# 06-RP2040.net
KiCad netlist of a schematic drawn in Altium Designer
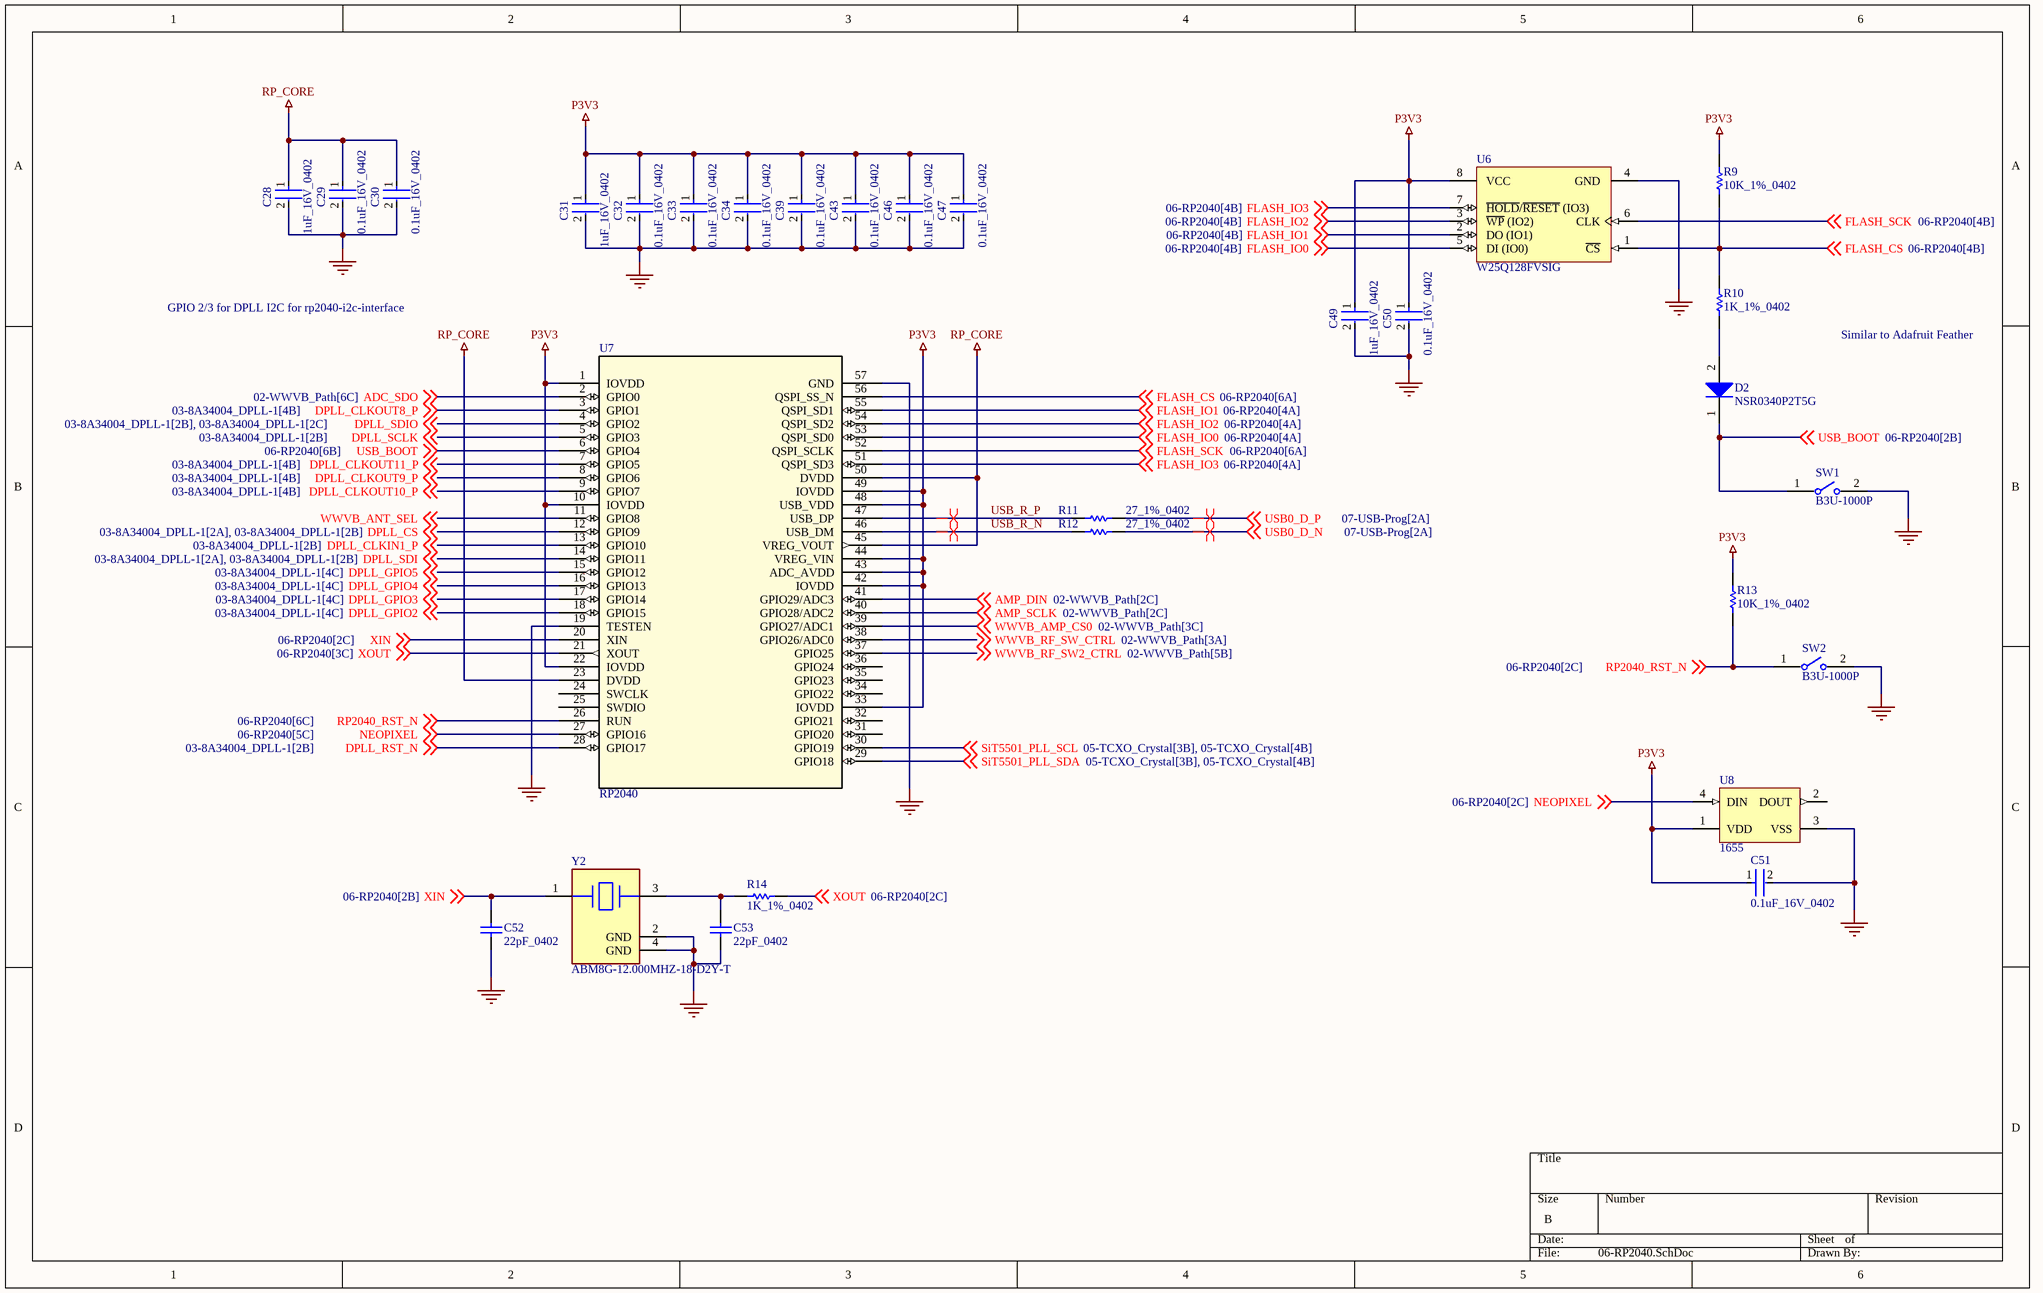
[diagram p0: 06-RP2040.SchDoc]

(export (version "E")
  (design (tool "Eeschema 10.0.6"))
  (components
    (comp (ref "C28")
      (value "1uF_16V_0402")
      (footprint "FP-0402-L_1_0_0_05-W_0_5-IPC_A")
      (description "None")
      (fields (field (name "TOLERANCE") "10%"))
      (libsource (lib "Altium Content Vault") (part "b4654b650e69147ec39a6b967a45e02"))
    )
    (comp (ref "C29")
      (value "0.1uF_16V_0402")
      (footprint "FP-C0402-BB-MFG")
      (description "CAP CER 0.1UF 16V 5% X7R 0402")
      (fields
        (field (name "MANUFACTURER") "Kemet")
        (field (name "MANUFACTURER PART NUMBER") "C0402C104J4RACTU")
      )
      (libsource (lib "Altium Content Vault") (part "b4654b650e69147ec39a6b967a45e02"))
    )
    (comp (ref "C30")
      (value "0.1uF_16V_0402")
      (footprint "FP-C0402-BB-MFG")
      (description "CAP CER 0.1UF 16V 5% X7R 0402")
      (fields
        (field (name "MANUFACTURER") "Kemet")
        (field (name "MANUFACTURER PART NUMBER") "C0402C104J4RACTU")
      )
      (libsource (lib "Altium Content Vault") (part "b4654b650e69147ec39a6b967a45e02"))
    )
    (comp (ref "C31")
      (value "1uF_16V_0402")
      (footprint "FP-0402-L_1_0_0_05-W_0_5-IPC_A")
      (description "None")
      (fields (field (name "TOLERANCE") "10%"))
      (libsource (lib "Altium Content Vault") (part "b4654b650e69147ec39a6b967a45e02"))
    )
    (comp (ref "C32")
      (value "0.1uF_16V_0402")
      (footprint "FP-C0402-BB-MFG")
      (description "CAP CER 0.1UF 16V 5% X7R 0402")
      (fields
        (field (name "MANUFACTURER") "Kemet")
        (field (name "MANUFACTURER PART NUMBER") "C0402C104J4RACTU")
      )
      (libsource (lib "Altium Content Vault") (part "b4654b650e69147ec39a6b967a45e02"))
    )
    (comp (ref "C33")
      (value "0.1uF_16V_0402")
      (footprint "FP-C0402-BB-MFG")
      (description "CAP CER 0.1UF 16V 5% X7R 0402")
      (fields
        (field (name "MANUFACTURER") "Kemet")
        (field (name "MANUFACTURER PART NUMBER") "C0402C104J4RACTU")
      )
      (libsource (lib "Altium Content Vault") (part "b4654b650e69147ec39a6b967a45e02"))
    )
    (comp (ref "C34")
      (value "0.1uF_16V_0402")
      (footprint "FP-C0402-BB-MFG")
      (description "CAP CER 0.1UF 16V 5% X7R 0402")
      (fields
        (field (name "MANUFACTURER") "Kemet")
        (field (name "MANUFACTURER PART NUMBER") "C0402C104J4RACTU")
      )
      (libsource (lib "Altium Content Vault") (part "b4654b650e69147ec39a6b967a45e02"))
    )
    (comp (ref "C39")
      (value "0.1uF_16V_0402")
      (footprint "FP-C0402-BB-MFG")
      (description "CAP CER 0.1UF 16V 5% X7R 0402")
      (fields
        (field (name "MANUFACTURER") "Kemet")
        (field (name "MANUFACTURER PART NUMBER") "C0402C104J4RACTU")
      )
      (libsource (lib "Altium Content Vault") (part "b4654b650e69147ec39a6b967a45e02"))
    )
    (comp (ref "C43")
      (value "0.1uF_16V_0402")
      (footprint "FP-C0402-BB-MFG")
      (description "CAP CER 0.1UF 16V 5% X7R 0402")
      (fields
        (field (name "MANUFACTURER") "Kemet")
        (field (name "MANUFACTURER PART NUMBER") "C0402C104J4RACTU")
      )
      (libsource (lib "Altium Content Vault") (part "b4654b650e69147ec39a6b967a45e02"))
    )
    (comp (ref "C46")
      (value "0.1uF_16V_0402")
      (footprint "FP-C0402-BB-MFG")
      (description "CAP CER 0.1UF 16V 5% X7R 0402")
      (fields
        (field (name "MANUFACTURER") "Kemet")
        (field (name "MANUFACTURER PART NUMBER") "C0402C104J4RACTU")
      )
      (libsource (lib "Altium Content Vault") (part "b4654b650e69147ec39a6b967a45e02"))
    )
    (comp (ref "C47")
      (value "0.1uF_16V_0402")
      (footprint "FP-C0402-BB-MFG")
      (description "CAP CER 0.1UF 16V 5% X7R 0402")
      (fields
        (field (name "MANUFACTURER") "Kemet")
        (field (name "MANUFACTURER PART NUMBER") "C0402C104J4RACTU")
      )
      (libsource (lib "Altium Content Vault") (part "b4654b650e69147ec39a6b967a45e02"))
    )
    (comp (ref "C49")
      (value "1uF_16V_0402")
      (footprint "FP-0402-L_1_0_0_05-W_0_5-IPC_A")
      (description "None")
      (fields (field (name "TOLERANCE") "10%"))
      (libsource (lib "Altium Content Vault") (part "b4654b650e69147ec39a6b967a45e02"))
    )
    (comp (ref "C50")
      (value "0.1uF_16V_0402")
      (footprint "FP-C0402-BB-MFG")
      (description "CAP CER 0.1UF 16V 5% X7R 0402")
      (fields
        (field (name "MANUFACTURER") "Kemet")
        (field (name "MANUFACTURER PART NUMBER") "C0402C104J4RACTU")
      )
      (libsource (lib "Altium Content Vault") (part "b4654b650e69147ec39a6b967a45e02"))
    )
    (comp (ref "C51")
      (value "0.1uF_16V_0402")
      (footprint "FP-C0402-BB-MFG")
      (description "CAP CER 0.1UF 16V 5% X7R 0402")
      (fields
        (field (name "MANUFACTURER") "Kemet")
        (field (name "MANUFACTURER PART NUMBER") "C0402C104J4RACTU")
      )
      (libsource (lib "Altium Content Vault") (part "b4654b650e69147ec39a6b967a45e02"))
    )
    (comp (ref "C52")
      (value "22pF_0402")
      (footprint "CAPC1005X55X25ML05T05")
      (description "Chip Capacitor, 22 pF, +/- 5%, 50 V, -55 to 125 degC, 0402 (1005 Metric), RoHS, Tape and Reel")
      (fields (field (name "MANUFACTURER") "Yageo") (field (name "TOLERANCE") "5%"))
      (libsource (lib "Altium Content Vault") (part "CAP-NP-2"))
    )
    (comp (ref "C53")
      (value "22pF_0402")
      (footprint "CAPC1005X55X25ML05T05")
      (description "Chip Capacitor, 22 pF, +/- 5%, 50 V, -55 to 125 degC, 0402 (1005 Metric), RoHS, Tape and Reel")
      (fields (field (name "MANUFACTURER") "Yageo") (field (name "TOLERANCE") "5%"))
      (libsource (lib "Altium Content Vault") (part "CAP-NP-2"))
    )
    (comp (ref "D2")
      (value "NSR0340P2T5G")
      (footprint "ONSC-SOD-923-2-514AB-01_B_V")
      (description "Schottky Barrier Diode, 2-Pin SOD-923, Pb-Free, Tape and Reel")
      (fields (field (name "MANUFACTURER") "On Semiconductor"))
      (libsource (lib "Altium Content Vault") (part "ONSC-D-K1A2-2"))
    )
    (comp (ref "R9")
      (value "10K_1%_0402")
      (footprint "RESC1005X40X25NL10T10")
      (fields (field (name "MANUFACTURER") "Bourns") (field (name "PART NUMBER") "CR0402-FX-1002GLF"))
      (libsource (lib "Altium Content Vault") (part "RES"))
    )
    (comp (ref "R10")
      (value "1K_1%_0402")
      (footprint "RESC1005X40X25LL10T10")
      (fields (field (name "PART NUMBER") "CR0402-FX-1001GLF") (field (name "MANUFACTURER") "Bourns"))
      (libsource (lib "Altium Content Vault") (part "RES"))
    )
    (comp (ref "R11")
      (value "27_1%_0402")
      (footprint "RESC1005X40X25LL05T10")
      (fields (field (name "PART NUMBER") "RC0402FR-0727RL") (field (name "MANUFACTURER") "Yageo / Phycomp"))
      (libsource (lib "Altium Content Vault") (part "RES"))
    )
    (comp (ref "R12")
      (value "27_1%_0402")
      (footprint "RESC1005X40X25LL05T10")
      (fields (field (name "PART NUMBER") "RC0402FR-0727RL") (field (name "MANUFACTURER") "Yageo / Phycomp"))
      (libsource (lib "Altium Content Vault") (part "RES"))
    )
    (comp (ref "R13")
      (value "10K_1%_0402")
      (footprint "RESC1005X40X25NL10T10")
      (fields (field (name "MANUFACTURER") "Bourns") (field (name "PART NUMBER") "CR0402-FX-1002GLF"))
      (libsource (lib "Altium Content Vault") (part "RES"))
    )
    (comp (ref "R14")
      (value "1K_1%_0402")
      (footprint "RESC1005X40X25LL10T10")
      (fields (field (name "PART NUMBER") "CR0402-FX-1001GLF") (field (name "MANUFACTURER") "Bourns"))
      (libsource (lib "Altium Content Vault") (part "RES"))
    )
    (comp (ref "SW1")
      (value "B3U-1000P")
      (footprint "FP-B3U-1000P-MFG")
      (description "SWITCH TACTILE SPST-NO 0.05A 12V")
      (libsource (lib "Altium Content Vault") (part "ae622034201233ca1abcedc05908f33"))
    )
    (comp (ref "SW2")
      (value "B3U-1000P")
      (footprint "FP-B3U-1000P-MFG")
      (description "SWITCH TACTILE SPST-NO 0.05A 12V")
      (libsource (lib "Altium Content Vault") (part "ae622034201233ca1abcedc05908f33"))
    )
    (comp (ref "U6")
      (value "W25Q128FVSIG")
      (footprint "WINB-SOIC-8_M")
      (fields (field (name "MANUFACTURER") "Winbond"))
      (libsource (lib "Altium Content Vault") (part "WINB-W25Q128FVSIG-SOIC-8"))
    )
    (comp (ref "U7")
      (value "RP2040")
      (footprint "IC57_RP2040")
      (description "No Description Available")
      (libsource (lib "RP2040") (part "RP2040"))
    )
    (comp (ref "U8")
      (value "1655")
      (footprint "ADA-RGB-1655_V")
      (fields (field (name "MANUFACTURER") "Adafruit-Industries-LLC"))
      (libsource (lib "Altium Content Vault") (part "ADA-RGB-1655-4"))
    )
    (comp (ref "Y2")
      (value "ABM8G-12.000MHZ-18-D2Y-T")
      (footprint "FP-ABM8G-MFG")
      (description "Crystal 12MHz ±20ppm (Tol) ±30ppm (Stability) 18pF FUND 120Ω 4-Pin SMD T/R")
      (fields (field (name "TOLERANCE") "20ppm"))
      (libsource (lib "Altium Content Vault") (part "48e526d86b7f2615d98721063c72f49"))
    )
  )
  (nets
    (net (code "1") (name "/USB_R_N") (class "Default")
      (node (ref "R12") (pin "1") (pinfunction "1_1") (pintype "passive"))
      (node (ref "U7") (pin "46") (pinfunction "USB_DM_46") (pintype "passive"))
    )
    (net (code "2") (name "/USB_R_P") (class "Default")
      (node (ref "R11") (pin "1") (pinfunction "1_1") (pintype "passive"))
      (node (ref "U7") (pin "47") (pinfunction "USB_DP_47") (pintype "passive"))
    )
    (net (code "3") (name "ADC_SDO") (class "Default")
      (node (ref "U7") (pin "2") (pinfunction "GPIO0_2") (pintype "bidirectional"))
    )
    (net (code "4") (name "AMP_DIN") (class "Default")
      (node (ref "U7") (pin "41") (pinfunction "GPIO29/ADC3_41") (pintype "bidirectional"))
    )
    (net (code "5") (name "AMP_SCLK") (class "Default")
      (node (ref "U7") (pin "40") (pinfunction "GPIO28/ADC2_40") (pintype "bidirectional"))
    )
    (net (code "6") (name "DPLL_CLKIN1_P") (class "Default")
      (node (ref "U7") (pin "13") (pinfunction "GPIO10_13") (pintype "bidirectional"))
    )
    (net (code "7") (name "DPLL_CLKOUT8_P") (class "Default")
      (node (ref "U7") (pin "3") (pinfunction "GPIO1_3") (pintype "bidirectional"))
    )
    (net (code "8") (name "DPLL_CLKOUT9_P") (class "Default")
      (node (ref "U7") (pin "8") (pinfunction "GPIO6_8") (pintype "bidirectional"))
    )
    (net (code "9") (name "DPLL_CLKOUT10_P") (class "Default")
      (node (ref "U7") (pin "9") (pinfunction "GPIO7_9") (pintype "bidirectional"))
    )
    (net (code "10") (name "DPLL_CLKOUT11_P") (class "Default")
      (node (ref "U7") (pin "7") (pinfunction "GPIO5_7") (pintype "bidirectional"))
    )
    (net (code "11") (name "DPLL_CS") (class "Default")
      (node (ref "U7") (pin "12") (pinfunction "GPIO9_12") (pintype "bidirectional"))
    )
    (net (code "12") (name "DPLL_GPIO2") (class "Default")
      (node (ref "U7") (pin "18") (pinfunction "GPIO15_18") (pintype "bidirectional"))
    )
    (net (code "13") (name "DPLL_GPIO3") (class "Default")
      (node (ref "U7") (pin "17") (pinfunction "GPIO14_17") (pintype "bidirectional"))
    )
    (net (code "14") (name "DPLL_GPIO4") (class "Default")
      (node (ref "U7") (pin "16") (pinfunction "GPIO13_16") (pintype "bidirectional"))
    )
    (net (code "15") (name "DPLL_GPIO5") (class "Default")
      (node (ref "U7") (pin "15") (pinfunction "GPIO12_15") (pintype "bidirectional"))
    )
    (net (code "16") (name "DPLL_RST_N") (class "Default")
      (node (ref "U7") (pin "28") (pinfunction "GPIO17_28") (pintype "bidirectional"))
    )
    (net (code "17") (name "DPLL_SCLK") (class "Default")
      (node (ref "U7") (pin "5") (pinfunction "GPIO3_5") (pintype "bidirectional"))
    )
    (net (code "18") (name "DPLL_SDI") (class "Default")
      (node (ref "U7") (pin "14") (pinfunction "GPIO11_14") (pintype "bidirectional"))
    )
    (net (code "19") (name "DPLL_SDIO") (class "Default")
      (node (ref "U7") (pin "4") (pinfunction "GPIO2_4") (pintype "bidirectional"))
    )
    (net (code "20") (name "FLASH_CS") (class "Default")
      (node (ref "R10") (pin "2") (pinfunction "2_2") (pintype "passive"))
      (node (ref "R9") (pin "2") (pinfunction "2_2") (pintype "passive"))
      (node (ref "U6") (pin "1") (pinfunction "~{CS}_1") (pintype "input"))
      (node (ref "U7") (pin "56") (pinfunction "QSPI_SS_N_56") (pintype "passive"))
    )
    (net (code "21") (name "FLASH_IO0") (class "Default")
      (node (ref "U6") (pin "5") (pinfunction "DI_(IO0)_5") (pintype "bidirectional"))
      (node (ref "U7") (pin "53") (pinfunction "QSPI_SD0_53") (pintype "bidirectional"))
    )
    (net (code "22") (name "FLASH_IO1") (class "Default")
      (node (ref "U6") (pin "2") (pinfunction "DO_(IO1)_2") (pintype "bidirectional"))
      (node (ref "U7") (pin "55") (pinfunction "QSPI_SD1_55") (pintype "bidirectional"))
    )
    (net (code "23") (name "FLASH_IO2") (class "Default")
      (node (ref "U6") (pin "3") (pinfunction "~{WP}_(IO2)_3") (pintype "bidirectional"))
      (node (ref "U7") (pin "54") (pinfunction "QSPI_SD2_54") (pintype "bidirectional"))
    )
    (net (code "24") (name "FLASH_IO3") (class "Default")
      (node (ref "U6") (pin "7") (pinfunction "~{HOLD}/~{RESET}_(IO3)_7") (pintype "bidirectional"))
      (node (ref "U7") (pin "51") (pinfunction "QSPI_SD3_51") (pintype "bidirectional"))
    )
    (net (code "25") (name "FLASH_SCK") (class "Default")
      (node (ref "U6") (pin "6") (pinfunction "CLK_6") (pintype "input"))
      (node (ref "U7") (pin "52") (pinfunction "QSPI_SCLK_52") (pintype "passive"))
    )
    (net (code "26") (name "GND") (class "Default")
      (node (ref "C28") (pin "2") (pinfunction "2_2") (pintype "passive"))
      (node (ref "C29") (pin "2") (pinfunction "2_2") (pintype "passive"))
      (node (ref "C30") (pin "2") (pinfunction "2_2") (pintype "passive"))
      (node (ref "C31") (pin "2") (pinfunction "2_2") (pintype "passive"))
      (node (ref "C32") (pin "2") (pinfunction "2_2") (pintype "passive"))
      (node (ref "C33") (pin "2") (pinfunction "2_2") (pintype "passive"))
      (node (ref "C34") (pin "2") (pinfunction "2_2") (pintype "passive"))
      (node (ref "C39") (pin "2") (pinfunction "2_2") (pintype "passive"))
      (node (ref "C43") (pin "2") (pinfunction "2_2") (pintype "passive"))
      (node (ref "C46") (pin "2") (pinfunction "2_2") (pintype "passive"))
      (node (ref "C47") (pin "2") (pinfunction "2_2") (pintype "passive"))
      (node (ref "C49") (pin "2") (pinfunction "2_2") (pintype "passive"))
      (node (ref "C50") (pin "2") (pinfunction "2_2") (pintype "passive"))
      (node (ref "C51") (pin "2") (pinfunction "2_2") (pintype "passive"))
      (node (ref "C52") (pin "1") (pinfunction "1_1") (pintype "passive"))
      (node (ref "C53") (pin "1") (pinfunction "1_1") (pintype "passive"))
      (node (ref "SW1") (pin "2") (pinfunction "2_2") (pintype "passive"))
      (node (ref "SW2") (pin "2") (pinfunction "2_2") (pintype "passive"))
      (node (ref "U6") (pin "4") (pinfunction "GND_4") (pintype "power_in"))
      (node (ref "U7") (pin "19") (pinfunction "TESTEN_19") (pintype "passive"))
      (node (ref "U7") (pin "57") (pinfunction "GND_57") (pintype "power_in"))
      (node (ref "U8") (pin "3") (pinfunction "VSS_3") (pintype "power_in"))
      (node (ref "Y2") (pin "2") (pinfunction "GND_2") (pintype "power_in"))
      (node (ref "Y2") (pin "4") (pinfunction "GND_4") (pintype "power_in"))
    )
    (net (code "27") (name "NEOPIXEL") (class "Default")
      (node (ref "U7") (pin "27") (pinfunction "GPIO16_27") (pintype "bidirectional"))
      (node (ref "U8") (pin "4") (pinfunction "DIN_4") (pintype "input"))
    )
    (net (code "28") (name "Net-(C53-Pad2)") (class "Default")
      (node (ref "C53") (pin "2") (pinfunction "2_2") (pintype "passive"))
      (node (ref "R14") (pin "1") (pinfunction "1_1") (pintype "passive"))
      (node (ref "Y2") (pin "3") (pinfunction "3_3") (pintype "passive"))
    )
    (net (code "29") (name "Net-(D2-A)") (class "Default")
      (node (ref "D2") (pin "2") (pinfunction "A_2") (pintype "passive"))
      (node (ref "R10") (pin "1") (pinfunction "1_1") (pintype "passive"))
    )
    (net (code "30") (name "P3V3") (class "Default")
      (node (ref "C31") (pin "1") (pinfunction "1_1") (pintype "passive"))
      (node (ref "C32") (pin "1") (pinfunction "1_1") (pintype "passive"))
      (node (ref "C33") (pin "1") (pinfunction "1_1") (pintype "passive"))
      (node (ref "C34") (pin "1") (pinfunction "1_1") (pintype "passive"))
      (node (ref "C39") (pin "1") (pinfunction "1_1") (pintype "passive"))
      (node (ref "C43") (pin "1") (pinfunction "1_1") (pintype "passive"))
      (node (ref "C46") (pin "1") (pinfunction "1_1") (pintype "passive"))
      (node (ref "C47") (pin "1") (pinfunction "1_1") (pintype "passive"))
      (node (ref "C49") (pin "1") (pinfunction "1_1") (pintype "passive"))
      (node (ref "C50") (pin "1") (pinfunction "1_1") (pintype "passive"))
      (node (ref "C51") (pin "1") (pinfunction "1_1") (pintype "passive"))
      (node (ref "R13") (pin "1") (pinfunction "1_1") (pintype "passive"))
      (node (ref "R9") (pin "1") (pinfunction "1_1") (pintype "passive"))
      (node (ref "U6") (pin "8") (pinfunction "VCC_8") (pintype "power_in"))
      (node (ref "U7") (pin "1") (pinfunction "IOVDD_1") (pintype "power_in"))
      (node (ref "U7") (pin "10") (pinfunction "IOVDD_10") (pintype "power_in"))
      (node (ref "U7") (pin "22") (pinfunction "IOVDD_22") (pintype "power_in"))
      (node (ref "U7") (pin "33") (pinfunction "IOVDD_33") (pintype "power_in"))
      (node (ref "U7") (pin "42") (pinfunction "IOVDD_42") (pintype "power_in"))
      (node (ref "U7") (pin "43") (pinfunction "ADC_AVDD_43") (pintype "power_in"))
      (node (ref "U7") (pin "44") (pinfunction "VREG_VIN_44") (pintype "passive"))
      (node (ref "U7") (pin "48") (pinfunction "USB_VDD_48") (pintype "power_in"))
      (node (ref "U7") (pin "49") (pinfunction "IOVDD_49") (pintype "power_in"))
      (node (ref "U8") (pin "1") (pinfunction "VDD_1") (pintype "power_in"))
    )
    (net (code "31") (name "RP2040_RST_N") (class "Default")
      (node (ref "R13") (pin "2") (pinfunction "2_2") (pintype "passive"))
      (node (ref "SW2") (pin "1") (pinfunction "1_1") (pintype "passive"))
      (node (ref "U7") (pin "26") (pinfunction "RUN_26") (pintype "passive"))
    )
    (net (code "32") (name "RP_CORE") (class "Default")
      (node (ref "C28") (pin "1") (pinfunction "1_1") (pintype "passive"))
      (node (ref "C29") (pin "1") (pinfunction "1_1") (pintype "passive"))
      (node (ref "C30") (pin "1") (pinfunction "1_1") (pintype "passive"))
      (node (ref "U7") (pin "23") (pinfunction "DVDD_23") (pintype "power_in"))
      (node (ref "U7") (pin "45") (pinfunction "VREG_VOUT_45") (pintype "output"))
      (node (ref "U7") (pin "50") (pinfunction "DVDD_50") (pintype "power_in"))
    )
    (net (code "33") (name "SiT5501_PLL_SCL") (class "Default")
      (node (ref "U7") (pin "30") (pinfunction "GPIO19_30") (pintype "bidirectional"))
    )
    (net (code "34") (name "SiT5501_PLL_SDA") (class "Default")
      (node (ref "U7") (pin "29") (pinfunction "GPIO18_29") (pintype "bidirectional"))
    )
    (net (code "35") (name "USB0_D_N") (class "Default")
      (node (ref "R12") (pin "2") (pinfunction "2_2") (pintype "passive"))
    )
    (net (code "36") (name "USB0_D_P") (class "Default")
      (node (ref "R11") (pin "2") (pinfunction "2_2") (pintype "passive"))
    )
    (net (code "37") (name "USB_BOOT") (class "Default")
      (node (ref "D2") (pin "1") (pinfunction "K_1") (pintype "passive"))
      (node (ref "SW1") (pin "1") (pinfunction "1_1") (pintype "passive"))
      (node (ref "U7") (pin "6") (pinfunction "GPIO4_6") (pintype "bidirectional"))
    )
    (net (code "38") (name "WWVB_AMP_CS0") (class "Default")
      (node (ref "U7") (pin "39") (pinfunction "GPIO27/ADC1_39") (pintype "bidirectional"))
    )
    (net (code "39") (name "WWVB_ANT_SEL") (class "Default")
      (node (ref "U7") (pin "11") (pinfunction "GPIO8_11") (pintype "bidirectional"))
    )
    (net (code "40") (name "WWVB_RF_SW2_CTRL") (class "Default")
      (node (ref "U7") (pin "37") (pinfunction "GPIO25_37") (pintype "bidirectional"))
    )
    (net (code "41") (name "WWVB_RF_SW_CTRL") (class "Default")
      (node (ref "U7") (pin "38") (pinfunction "GPIO26/ADC0_38") (pintype "bidirectional"))
    )
    (net (code "42") (name "XIN") (class "Default")
      (node (ref "C52") (pin "2") (pinfunction "2_2") (pintype "passive"))
      (node (ref "U7") (pin "20") (pinfunction "XIN_20") (pintype "passive"))
      (node (ref "Y2") (pin "1") (pinfunction "1_1") (pintype "passive"))
    )
    (net (code "43") (name "XOUT") (class "Default")
      (node (ref "R14") (pin "2") (pinfunction "2_2") (pintype "passive"))
      (node (ref "U7") (pin "21") (pinfunction "XOUT_21") (pintype "output"))
    )
    (net (code "44") (name "unconnected-(U7-GPIO20-Pad31)") (class "Default")
      (node (ref "U7") (pin "31") (pinfunction "GPIO20_31") (pintype "bidirectional"))
    )
    (net (code "45") (name "unconnected-(U7-GPIO21-Pad32)") (class "Default")
      (node (ref "U7") (pin "32") (pinfunction "GPIO21_32") (pintype "bidirectional"))
    )
    (net (code "46") (name "unconnected-(U7-GPIO22-Pad34)") (class "Default")
      (node (ref "U7") (pin "34") (pinfunction "GPIO22_34") (pintype "bidirectional"))
    )
    (net (code "47") (name "unconnected-(U7-GPIO23-Pad35)") (class "Default")
      (node (ref "U7") (pin "35") (pinfunction "GPIO23_35") (pintype "bidirectional"))
    )
    (net (code "48") (name "unconnected-(U7-GPIO24-Pad36)") (class "Default")
      (node (ref "U7") (pin "36") (pinfunction "GPIO24_36") (pintype "bidirectional"))
    )
    (net (code "49") (name "unconnected-(U7-SWCLK-Pad24)") (class "Default")
      (node (ref "U7") (pin "24") (pinfunction "SWCLK_24") (pintype "passive"))
    )
    (net (code "50") (name "unconnected-(U7-SWDIO-Pad25)") (class "Default")
      (node (ref "U7") (pin "25") (pinfunction "SWDIO_25") (pintype "passive"))
    )
    (net (code "51") (name "unconnected-(U8-DOUT-Pad2)") (class "Default")
      (node (ref "U8") (pin "2") (pinfunction "DOUT_2") (pintype "output"))
    )
  )
)
